# 555-Oscillator.net
KiCad netlist of a schematic drawn in EAGLE
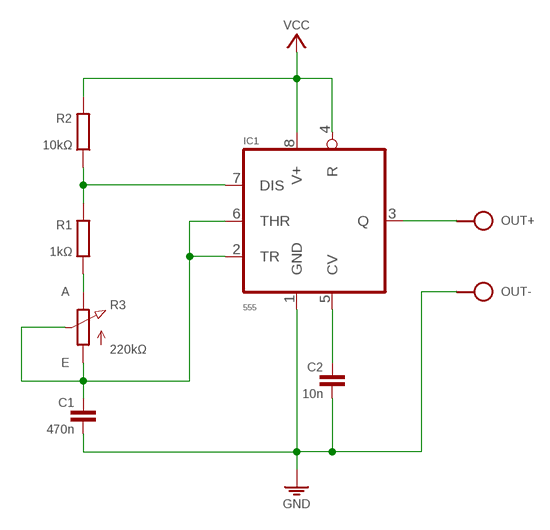
[diagram p0: schematic, sheet 1]

(export (version "E")
  (design (tool "Eeschema 10.0.6"))
  (components
    (comp (ref "C1")
      (value "470n")
      (footprint "eagle-import:C050-024X044_V")
      (libsource (lib "eagle-import") (part "C050-024X044/V"))
    )
    (comp (ref "C2")
      (value "10n")
      (footprint "eagle-import:C050-020X036_V")
      (libsource (lib "eagle-import") (part "C050-020X036/V"))
    )
    (comp (ref "IC1")
      (value "555")
      (footprint "eagle-import:DIL08")
      (libsource (lib "eagle-import") (part "555_ALT"))
    )
    (comp (ref "OUT")
      (value "SPAD+--+")
      (footprint "eagle-import:SPAD-+")
      (libsource (lib "eagle-import") (part "SPAD+--+"))
    )
    (comp (ref "R1")
      (value "1kΩ")
      (footprint "eagle-import:0207_10")
      (libsource (lib "eagle-import") (part "R0207/10"))
    )
    (comp (ref "R2")
      (value "10kΩ")
      (footprint "eagle-import:0207_10")
      (libsource (lib "eagle-import") (part "R0207/10"))
    )
    (comp (ref "R3")
      (value "220kΩ")
      (footprint "eagle-import:POT-V")
      (libsource (lib "eagle-import") (part "POT-V"))
    )
    (comp (ref "S1")
      (value "VCC_GNDPWR-R")
      (footprint "eagle-import:PWR-R")
      (libsource (lib "eagle-import") (part "VCC_GNDPWR-R"))
    )
  )
  (nets
    (net (code "1") (name "Net-(IC1-CV)") (class "Default")
      (node (ref "C2") (pin "1") (pinfunction "1_1") (pintype "passive"))
      (node (ref "IC1") (pin "5") (pinfunction "CV_5") (pintype "input"))
    )
    (net (code "2") (name "Net-(IC1-DIS)") (class "Default")
      (node (ref "IC1") (pin "7") (pinfunction "DIS_7") (pintype "passive"))
      (node (ref "R1") (pin "1") (pinfunction "2_1") (pintype "passive"))
      (node (ref "R2") (pin "2") (pinfunction "1_2") (pintype "passive"))
    )
    (net (code "3") (name "Net-(IC1-GND)") (class "Default")
      (node (ref "C1") (pin "2") (pinfunction "2_2") (pintype "passive"))
      (node (ref "C2") (pin "2") (pinfunction "2_2") (pintype "passive"))
      (node (ref "IC1") (pin "1") (pinfunction "GND_1") (pintype "power_in"))
      (node (ref "OUT") (pin "1") (pinfunction "P$1_1") (pintype "passive"))
      (node (ref "S1") (pin "1") (pinfunction "GND_1") (pintype "power_in"))
    )
    (net (code "4") (name "Net-(IC1-Q)") (class "Default")
      (node (ref "IC1") (pin "3") (pinfunction "Q_3") (pintype "output"))
      (node (ref "OUT") (pin "2") (pinfunction "P$1_2") (pintype "passive"))
    )
    (net (code "5") (name "Net-(IC1-R)") (class "Default")
      (node (ref "IC1") (pin "4") (pinfunction "R_4") (pintype "input"))
      (node (ref "IC1") (pin "8") (pinfunction "V+_8") (pintype "power_in"))
      (node (ref "R2") (pin "1") (pinfunction "2_1") (pintype "passive"))
      (node (ref "S1") (pin "2") (pinfunction "VCC_2") (pintype "power_in"))
    )
    (net (code "6") (name "Net-(IC1-THR)") (class "Default")
      (node (ref "C1") (pin "1") (pinfunction "1_1") (pintype "passive"))
      (node (ref "IC1") (pin "2") (pinfunction "TR_2") (pintype "input"))
      (node (ref "IC1") (pin "6") (pinfunction "THR_6") (pintype "input"))
      (node (ref "R3") (pin "A") (pinfunction "A_A") (pintype "passive"))
      (node (ref "R3") (pin "S") (pinfunction "S_S") (pintype "passive"))
    )
    (net (code "7") (name "Net-(R1-1)") (class "Default")
      (node (ref "R1") (pin "2") (pinfunction "1_2") (pintype "passive"))
      (node (ref "R3") (pin "E") (pinfunction "E_E") (pintype "passive"))
    )
  )
)
